# touch_pot.net
KiCad netlist of a schematic drawn in EAGLE
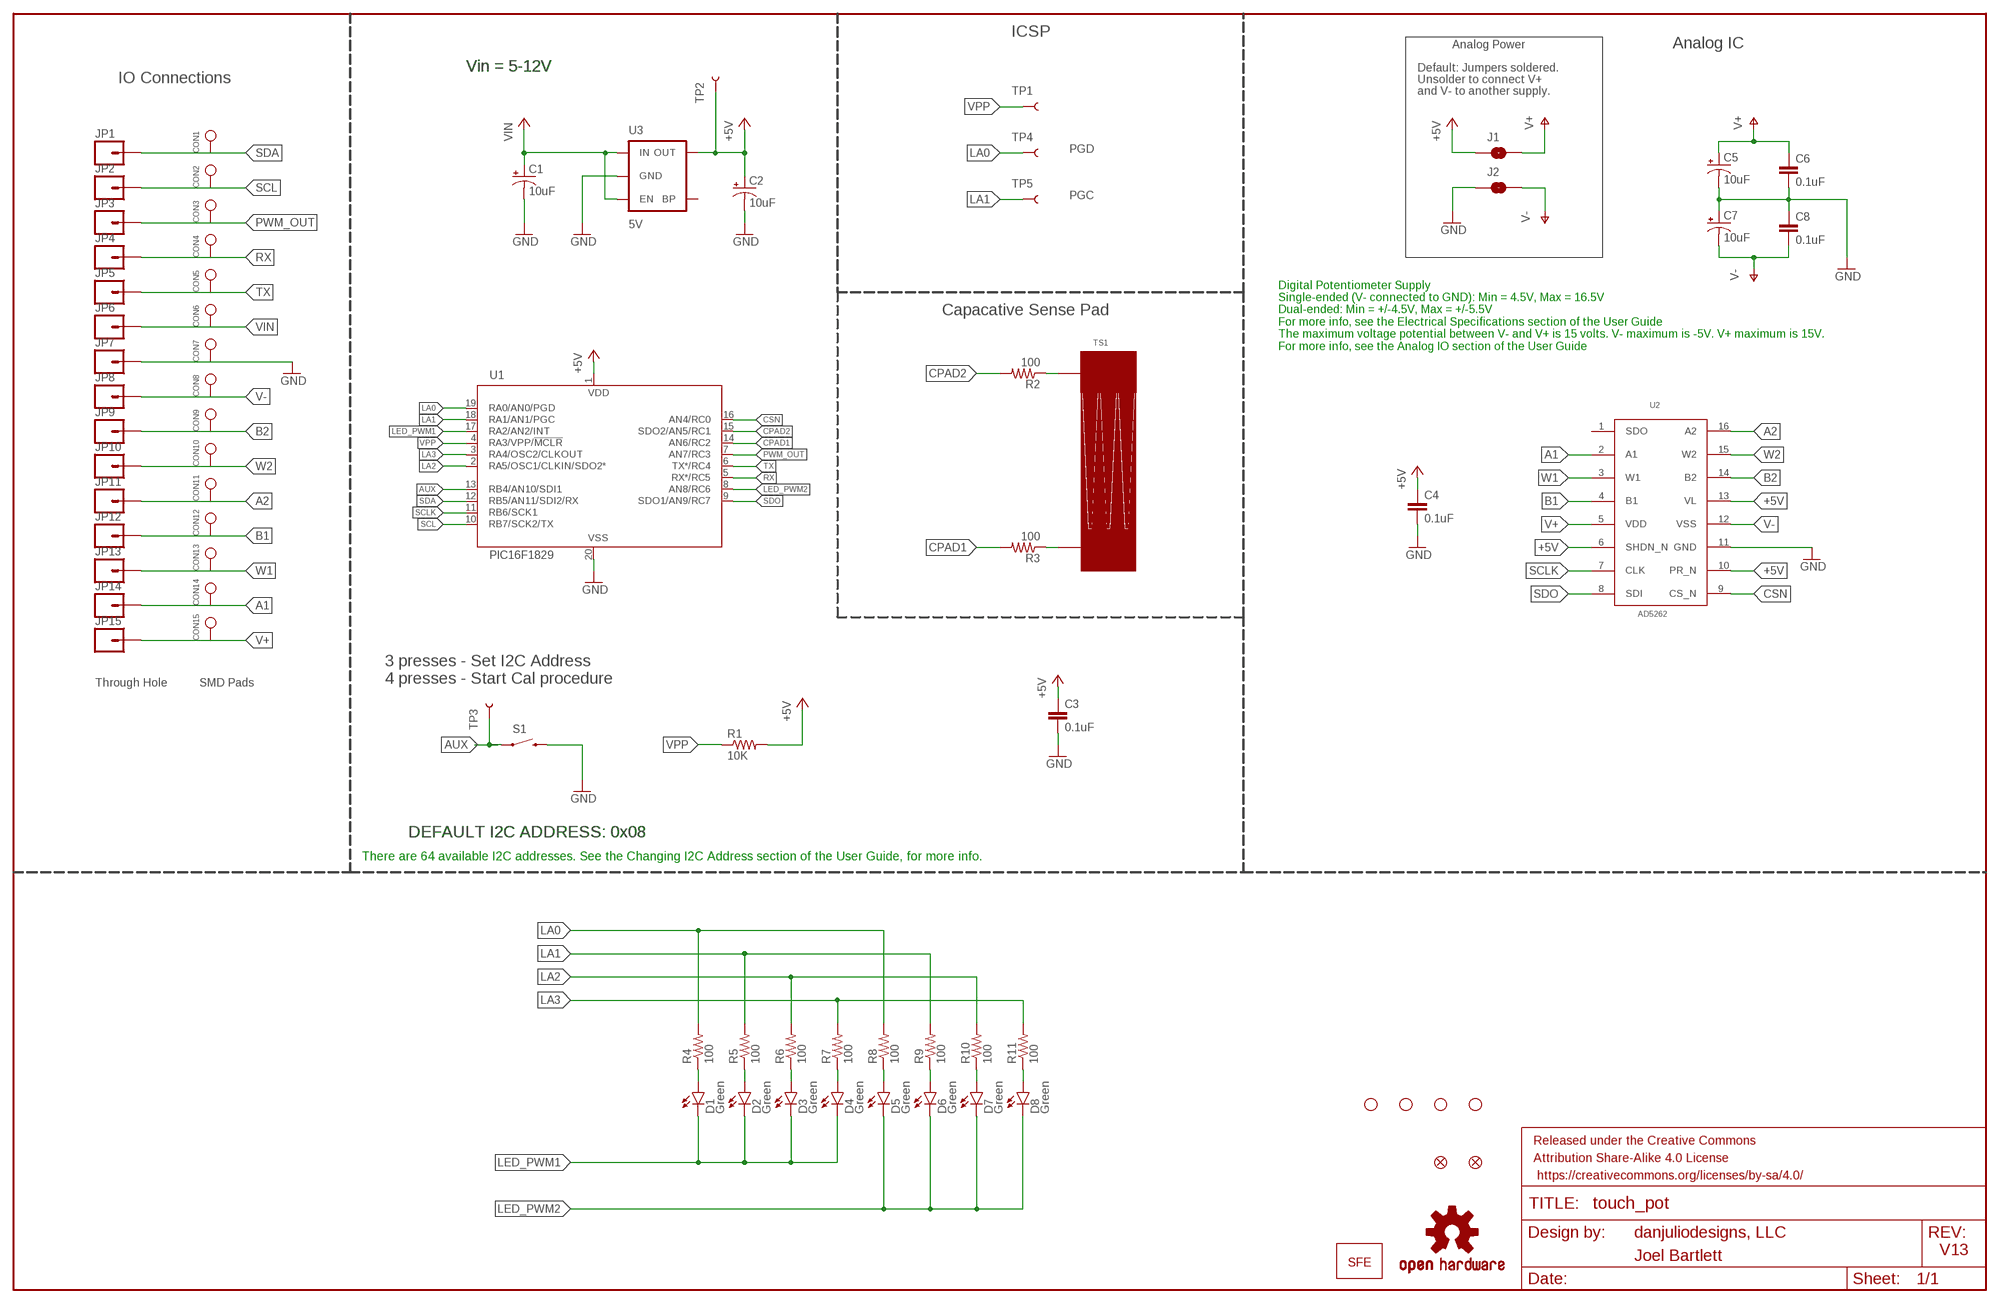
[diagram p0: schematic, sheet 1]

(export (version "E")
  (design (tool "Eeschema 10.0.6"))
  (components
    (comp (ref "C1")
      (value "10uF")
      (footprint "eagle-import:EIA3216")
      (libsource (lib "eagle-import") (part "10UF-16V-10%(TANT)"))
    )
    (comp (ref "C2")
      (value "10uF")
      (footprint "eagle-import:EIA3216")
      (libsource (lib "eagle-import") (part "10UF-16V-10%(TANT)"))
    )
    (comp (ref "C3")
      (value "0.1uF")
      (footprint "eagle-import:0603-CAP")
      (libsource (lib "eagle-import") (part "0.1UF-25V(+80/-20%)(0603)"))
    )
    (comp (ref "C4")
      (value "0.1uF")
      (footprint "eagle-import:0603-CAP")
      (libsource (lib "eagle-import") (part "0.1UF-25V(+80/-20%)(0603)"))
    )
    (comp (ref "C5")
      (value "10uF")
      (footprint "eagle-import:EIA3216")
      (libsource (lib "eagle-import") (part "10UF-16V-10%(TANT)"))
    )
    (comp (ref "C6")
      (value "0.1uF")
      (footprint "eagle-import:0603-CAP")
      (libsource (lib "eagle-import") (part "0.1UF-25V(+80/-20%)(0603)"))
    )
    (comp (ref "C7")
      (value "10uF")
      (footprint "eagle-import:EIA3216")
      (libsource (lib "eagle-import") (part "10UF-16V-10%(TANT)"))
    )
    (comp (ref "C8")
      (value "0.1uF")
      (footprint "eagle-import:0603-CAP")
      (libsource (lib "eagle-import") (part "0.1UF-25V(+80/-20%)(0603)"))
    )
    (comp (ref "CON1")
      (value "SINGLE_PADSMD")
      (footprint "eagle-import:2MM_SMD_PAD")
      (libsource (lib "eagle-import") (part "SINGLE_PADSMD"))
    )
    (comp (ref "CON2")
      (value "SINGLE_PADSMD")
      (footprint "eagle-import:2MM_SMD_PAD")
      (libsource (lib "eagle-import") (part "SINGLE_PADSMD"))
    )
    (comp (ref "CON3")
      (value "SINGLE_PADSMD")
      (footprint "eagle-import:2MM_SMD_PAD")
      (libsource (lib "eagle-import") (part "SINGLE_PADSMD"))
    )
    (comp (ref "CON4")
      (value "SINGLE_PADSMD")
      (footprint "eagle-import:2MM_SMD_PAD")
      (libsource (lib "eagle-import") (part "SINGLE_PADSMD"))
    )
    (comp (ref "CON5")
      (value "SINGLE_PADSMD")
      (footprint "eagle-import:2MM_SMD_PAD")
      (libsource (lib "eagle-import") (part "SINGLE_PADSMD"))
    )
    (comp (ref "CON6")
      (value "SINGLE_PADSMD")
      (footprint "eagle-import:2MM_SMD_PAD")
      (libsource (lib "eagle-import") (part "SINGLE_PADSMD"))
    )
    (comp (ref "CON7")
      (value "SINGLE_PADSMD")
      (footprint "eagle-import:2MM_SMD_PAD")
      (libsource (lib "eagle-import") (part "SINGLE_PADSMD"))
    )
    (comp (ref "CON8")
      (value "SINGLE_PADSMD")
      (footprint "eagle-import:2MM_SMD_PAD")
      (libsource (lib "eagle-import") (part "SINGLE_PADSMD"))
    )
    (comp (ref "CON9")
      (value "SINGLE_PADSMD")
      (footprint "eagle-import:2MM_SMD_PAD")
      (libsource (lib "eagle-import") (part "SINGLE_PADSMD"))
    )
    (comp (ref "CON10")
      (value "SINGLE_PADSMD")
      (footprint "eagle-import:2MM_SMD_PAD")
      (libsource (lib "eagle-import") (part "SINGLE_PADSMD"))
    )
    (comp (ref "CON11")
      (value "SINGLE_PADSMD")
      (footprint "eagle-import:2MM_SMD_PAD")
      (libsource (lib "eagle-import") (part "SINGLE_PADSMD"))
    )
    (comp (ref "CON12")
      (value "SINGLE_PADSMD")
      (footprint "eagle-import:2MM_SMD_PAD")
      (libsource (lib "eagle-import") (part "SINGLE_PADSMD"))
    )
    (comp (ref "CON13")
      (value "SINGLE_PADSMD")
      (footprint "eagle-import:2MM_SMD_PAD")
      (libsource (lib "eagle-import") (part "SINGLE_PADSMD"))
    )
    (comp (ref "CON14")
      (value "SINGLE_PADSMD")
      (footprint "eagle-import:2MM_SMD_PAD")
      (libsource (lib "eagle-import") (part "SINGLE_PADSMD"))
    )
    (comp (ref "CON15")
      (value "SINGLE_PADSMD")
      (footprint "eagle-import:2MM_SMD_PAD")
      (libsource (lib "eagle-import") (part "SINGLE_PADSMD"))
    )
    (comp (ref "D1")
      (value "Green")
      (footprint "eagle-import:LED-1206-BOTTOM")
      (libsource (lib "eagle-import") (part "LED-GREEN1206-BOTTOM"))
    )
    (comp (ref "D2")
      (value "Green")
      (footprint "eagle-import:LED-1206-BOTTOM")
      (libsource (lib "eagle-import") (part "LED-GREEN1206-BOTTOM"))
    )
    (comp (ref "D3")
      (value "Green")
      (footprint "eagle-import:LED-1206-BOTTOM")
      (libsource (lib "eagle-import") (part "LED-GREEN1206-BOTTOM"))
    )
    (comp (ref "D4")
      (value "Green")
      (footprint "eagle-import:LED-1206-BOTTOM")
      (libsource (lib "eagle-import") (part "LED-GREEN1206-BOTTOM"))
    )
    (comp (ref "D5")
      (value "Green")
      (footprint "eagle-import:LED-1206-BOTTOM")
      (libsource (lib "eagle-import") (part "LED-GREEN1206-BOTTOM"))
    )
    (comp (ref "D6")
      (value "Green")
      (footprint "eagle-import:LED-1206-BOTTOM")
      (libsource (lib "eagle-import") (part "LED-GREEN1206-BOTTOM"))
    )
    (comp (ref "D7")
      (value "Green")
      (footprint "eagle-import:LED-1206-BOTTOM")
      (libsource (lib "eagle-import") (part "LED-GREEN1206-BOTTOM"))
    )
    (comp (ref "D8")
      (value "Green")
      (footprint "eagle-import:LED-1206-BOTTOM")
      (libsource (lib "eagle-import") (part "LED-GREEN1206-BOTTOM"))
    )
    (comp (ref "FID1")
      (value "FIDUCIAL1X2")
      (footprint "eagle-import:FIDUCIAL-1X2")
      (libsource (lib "eagle-import") (part "FIDUCIAL1X2"))
    )
    (comp (ref "FID2")
      (value "FIDUCIAL1X2")
      (footprint "eagle-import:FIDUCIAL-1X2")
      (libsource (lib "eagle-import") (part "FIDUCIAL1X2"))
    )
    (comp (ref "FRAME3")
      (value "FRAME-LEDGER")
      (footprint "eagle-import:CREATIVE_COMMONS")
      (libsource (lib "eagle-import") (part "FRAME-LEDGER"))
    )
    (comp (ref "J1")
      (value "SJCLOSED")
      (footprint "eagle-import:SJ_2S")
      (libsource (lib "eagle-import") (part "SJCLOSED"))
    )
    (comp (ref "J2")
      (value "SJCLOSED")
      (footprint "eagle-import:SJ_2S")
      (libsource (lib "eagle-import") (part "SJCLOSED"))
    )
    (comp (ref "JP1")
      (value "M01SMDNS")
      (footprint "eagle-import:1X01NS")
      (libsource (lib "eagle-import") (part "M01SMDNS"))
    )
    (comp (ref "JP2")
      (value "M01SMDNS")
      (footprint "eagle-import:1X01NS")
      (libsource (lib "eagle-import") (part "M01SMDNS"))
    )
    (comp (ref "JP3")
      (value "M01SMDNS")
      (footprint "eagle-import:1X01NS")
      (libsource (lib "eagle-import") (part "M01SMDNS"))
    )
    (comp (ref "JP4")
      (value "M01SMDNS")
      (footprint "eagle-import:1X01NS")
      (libsource (lib "eagle-import") (part "M01SMDNS"))
    )
    (comp (ref "JP5")
      (value "M01SMDNS")
      (footprint "eagle-import:1X01NS")
      (libsource (lib "eagle-import") (part "M01SMDNS"))
    )
    (comp (ref "JP6")
      (value "M01SMDNS")
      (footprint "eagle-import:1X01NS")
      (libsource (lib "eagle-import") (part "M01SMDNS"))
    )
    (comp (ref "JP7")
      (value "M01SMDNS")
      (footprint "eagle-import:1X01NS")
      (libsource (lib "eagle-import") (part "M01SMDNS"))
    )
    (comp (ref "JP8")
      (value "M01SMDNS")
      (footprint "eagle-import:1X01NS")
      (libsource (lib "eagle-import") (part "M01SMDNS"))
    )
    (comp (ref "JP9")
      (value "M01SMDNS")
      (footprint "eagle-import:1X01NS")
      (libsource (lib "eagle-import") (part "M01SMDNS"))
    )
    (comp (ref "JP10")
      (value "M01SMDNS")
      (footprint "eagle-import:1X01NS")
      (libsource (lib "eagle-import") (part "M01SMDNS"))
    )
    (comp (ref "JP11")
      (value "M01SMDNS")
      (footprint "eagle-import:1X01NS")
      (libsource (lib "eagle-import") (part "M01SMDNS"))
    )
    (comp (ref "JP12")
      (value "M01SMDNS")
      (footprint "eagle-import:1X01NS")
      (libsource (lib "eagle-import") (part "M01SMDNS"))
    )
    (comp (ref "JP13")
      (value "M01SMDNS")
      (footprint "eagle-import:1X01NS")
      (libsource (lib "eagle-import") (part "M01SMDNS"))
    )
    (comp (ref "JP14")
      (value "M01SMDNS")
      (footprint "eagle-import:1X01NS")
      (libsource (lib "eagle-import") (part "M01SMDNS"))
    )
    (comp (ref "JP15")
      (value "M01SMDNS")
      (footprint "eagle-import:1X01NS")
      (libsource (lib "eagle-import") (part "M01SMDNS"))
    )
    (comp (ref "R1")
      (value "10K")
      (footprint "eagle-import:0603-RES")
      (libsource (lib "eagle-import") (part "10KOHM-1/10W-1%(0603)0603"))
    )
    (comp (ref "R2")
      (value "100")
      (footprint "eagle-import:0603-RES")
      (libsource (lib "eagle-import") (part "100OHM-1/10W-1%(0603)"))
    )
    (comp (ref "R3")
      (value "100")
      (footprint "eagle-import:0603-RES")
      (libsource (lib "eagle-import") (part "100OHM-1/10W-1%(0603)"))
    )
    (comp (ref "R4")
      (value "100")
      (footprint "eagle-import:0603-RES")
      (libsource (lib "eagle-import") (part "100OHM-1/10W-1%(0603)"))
    )
    (comp (ref "R5")
      (value "100")
      (footprint "eagle-import:0603-RES")
      (libsource (lib "eagle-import") (part "100OHM-1/10W-1%(0603)"))
    )
    (comp (ref "R6")
      (value "100")
      (footprint "eagle-import:0603-RES")
      (libsource (lib "eagle-import") (part "100OHM-1/10W-1%(0603)"))
    )
    (comp (ref "R7")
      (value "100")
      (footprint "eagle-import:0603-RES")
      (libsource (lib "eagle-import") (part "100OHM-1/10W-1%(0603)"))
    )
    (comp (ref "R8")
      (value "100")
      (footprint "eagle-import:0603-RES")
      (libsource (lib "eagle-import") (part "100OHM-1/10W-1%(0603)"))
    )
    (comp (ref "R9")
      (value "100")
      (footprint "eagle-import:0603-RES")
      (libsource (lib "eagle-import") (part "100OHM-1/10W-1%(0603)"))
    )
    (comp (ref "R10")
      (value "100")
      (footprint "eagle-import:0603-RES")
      (libsource (lib "eagle-import") (part "100OHM-1/10W-1%(0603)"))
    )
    (comp (ref "R11")
      (value "100")
      (footprint "eagle-import:0603-RES")
      (libsource (lib "eagle-import") (part "100OHM-1/10W-1%(0603)"))
    )
    (comp (ref "S1")
      (value "SWITCH-MOMENTARY-2SMD")
      (footprint "eagle-import:TACTILE-SWITCH-SMD")
      (libsource (lib "eagle-import") (part "SWITCH-MOMENTARY-2SMD"))
    )
    (comp (ref "STANDOFF1")
      (value "STAND-OFFTIGHT")
      (footprint "eagle-import:STAND-OFF-TIGHT")
      (libsource (lib "eagle-import") (part "STAND-OFFTIGHT"))
    )
    (comp (ref "STANDOFF2")
      (value "STAND-OFFTIGHT")
      (footprint "eagle-import:STAND-OFF-TIGHT")
      (libsource (lib "eagle-import") (part "STAND-OFFTIGHT"))
    )
    (comp (ref "STANDOFF3")
      (value "STAND-OFFTIGHT")
      (footprint "eagle-import:STAND-OFF-TIGHT")
      (libsource (lib "eagle-import") (part "STAND-OFFTIGHT"))
    )
    (comp (ref "STANDOFF4")
      (value "STAND-OFFTIGHT")
      (footprint "eagle-import:STAND-OFF-TIGHT")
      (libsource (lib "eagle-import") (part "STAND-OFFTIGHT"))
    )
    (comp (ref "TP1")
      (value "TEST-POINT3X4")
      (footprint "eagle-import:PAD.03X.04")
      (libsource (lib "eagle-import") (part "TEST-POINT3X4"))
    )
    (comp (ref "TP2")
      (value "TEST-POINT3X4")
      (footprint "eagle-import:PAD.03X.04")
      (libsource (lib "eagle-import") (part "TEST-POINT3X4"))
    )
    (comp (ref "TP3")
      (value "TEST-POINT3X4")
      (footprint "eagle-import:PAD.03X.04")
      (libsource (lib "eagle-import") (part "TEST-POINT3X4"))
    )
    (comp (ref "TP4")
      (value "TEST-POINT3X4")
      (footprint "eagle-import:PAD.03X.04")
      (libsource (lib "eagle-import") (part "TEST-POINT3X4"))
    )
    (comp (ref "TP5")
      (value "TEST-POINT3X4")
      (footprint "eagle-import:PAD.03X.04")
      (libsource (lib "eagle-import") (part "TEST-POINT3X4"))
    )
    (comp (ref "TS1")
      (value "2CH_LINEAR_TOUCH")
      (footprint "eagle-import:2CH_48MM_LINEAR_TOUCH")
      (libsource (lib "eagle-import") (part "2CH_LINEAR_TOUCH"))
    )
    (comp (ref "U$4")
      (value "OSHW-LOGOM")
      (footprint "eagle-import:OSHW-LOGO-M")
      (libsource (lib "eagle-import") (part "OSHW-LOGOM"))
    )
    (comp (ref "U$5")
      (value "SFE_LOGO_NAME_WEB")
      (footprint "eagle-import:SFE-NEW-WEBLOGO")
      (libsource (lib "eagle-import") (part "SFE_LOGO_NAME_WEB"))
    )
    (comp (ref "U1")
      (value "PIC16F1829")
      (footprint "eagle-import:SSOP20")
      (libsource (lib "eagle-import") (part "PIC16F1829"))
    )
    (comp (ref "U2")
      (value "AD5262")
      (footprint "eagle-import:SSOP16")
      (libsource (lib "eagle-import") (part "AD5262"))
    )
    (comp (ref "U3")
      (value "5V")
      (footprint "eagle-import:SOT23-5")
      (libsource (lib "eagle-import") (part "V_REG_MIC52055V"))
    )
  )
  (nets
    (net (code "1") (name "+5V") (class "Default")
      (node (ref "C2") (pin "A") (pinfunction "+_A") (pintype "passive"))
      (node (ref "C3") (pin "1") (pinfunction "1_1") (pintype "passive"))
      (node (ref "C4") (pin "1") (pinfunction "1_1") (pintype "passive"))
      (node (ref "J1") (pin "1") (pinfunction "1_1") (pintype "passive"))
      (node (ref "R1") (pin "2") (pinfunction "2_2") (pintype "passive"))
      (node (ref "TP2") (pin "P$1") (pinfunction "1_P$1") (pintype "bidirectional"))
      (node (ref "U1") (pin "1") (pinfunction "VDD_1") (pintype "power_in"))
      (node (ref "U2") (pin "10") (pinfunction "PR_N_10") (pintype "input"))
      (node (ref "U2") (pin "13") (pinfunction "VL_13") (pintype "power_in"))
      (node (ref "U2") (pin "6") (pinfunction "SHDN_N_6") (pintype "input"))
      (node (ref "U3") (pin "5") (pinfunction "OUT_5") (pintype "passive"))
    )
    (net (code "2") (name "A1") (class "Default")
      (node (ref "CON14") (pin "P$1") (pinfunction "P$1_P$1") (pintype "passive"))
      (node (ref "JP14") (pin "1") (pinfunction "1_1") (pintype "passive"))
      (node (ref "U2") (pin "2") (pinfunction "A1_2") (pintype "passive"))
    )
    (net (code "3") (name "A2") (class "Default")
      (node (ref "CON11") (pin "P$1") (pinfunction "P$1_P$1") (pintype "passive"))
      (node (ref "JP11") (pin "1") (pinfunction "1_1") (pintype "passive"))
      (node (ref "U2") (pin "16") (pinfunction "A2_16") (pintype "passive"))
    )
    (net (code "4") (name "AUX") (class "Default")
      (node (ref "S1") (pin "1") (pinfunction "1_1") (pintype "passive"))
      (node (ref "TP3") (pin "P$1") (pinfunction "1_P$1") (pintype "bidirectional"))
      (node (ref "U1") (pin "13") (pinfunction "RB4/AN10/SDI1_13") (pintype "bidirectional"))
    )
    (net (code "5") (name "B1") (class "Default")
      (node (ref "CON12") (pin "P$1") (pinfunction "P$1_P$1") (pintype "passive"))
      (node (ref "JP12") (pin "1") (pinfunction "1_1") (pintype "passive"))
      (node (ref "U2") (pin "4") (pinfunction "B1_4") (pintype "passive"))
    )
    (net (code "6") (name "B2") (class "Default")
      (node (ref "CON9") (pin "P$1") (pinfunction "P$1_P$1") (pintype "passive"))
      (node (ref "JP9") (pin "1") (pinfunction "1_1") (pintype "passive"))
      (node (ref "U2") (pin "14") (pinfunction "B2_14") (pintype "passive"))
    )
    (net (code "7") (name "CPAD1") (class "Default")
      (node (ref "R3") (pin "2") (pinfunction "2_2") (pintype "passive"))
      (node (ref "U1") (pin "14") (pinfunction "AN6/RC2_14") (pintype "bidirectional"))
    )
    (net (code "8") (name "CPAD2") (class "Default")
      (node (ref "R2") (pin "2") (pinfunction "2_2") (pintype "passive"))
      (node (ref "U1") (pin "15") (pinfunction "SDO2/AN5/RC1_15") (pintype "bidirectional"))
    )
    (net (code "9") (name "CSN") (class "Default")
      (node (ref "U1") (pin "16") (pinfunction "AN4/RC0_16") (pintype "bidirectional"))
      (node (ref "U2") (pin "9") (pinfunction "CS_N_9") (pintype "input"))
    )
    (net (code "10") (name "GND") (class "Default")
      (node (ref "C1") (pin "C") (pinfunction "-_C") (pintype "passive"))
      (node (ref "C2") (pin "C") (pinfunction "-_C") (pintype "passive"))
      (node (ref "C3") (pin "2") (pinfunction "2_2") (pintype "passive"))
      (node (ref "C4") (pin "2") (pinfunction "2_2") (pintype "passive"))
      (node (ref "C5") (pin "C") (pinfunction "-_C") (pintype "passive"))
      (node (ref "C6") (pin "2") (pinfunction "2_2") (pintype "passive"))
      (node (ref "C7") (pin "A") (pinfunction "+_A") (pintype "passive"))
      (node (ref "C8") (pin "1") (pinfunction "1_1") (pintype "passive"))
      (node (ref "CON7") (pin "P$1") (pinfunction "P$1_P$1") (pintype "passive"))
      (node (ref "J2") (pin "1") (pinfunction "1_1") (pintype "passive"))
      (node (ref "JP7") (pin "1") (pinfunction "1_1") (pintype "passive"))
      (node (ref "S1") (pin "3") (pinfunction "2_3") (pintype "passive"))
      (node (ref "U1") (pin "20") (pinfunction "VSS_20") (pintype "power_in"))
      (node (ref "U2") (pin "11") (pinfunction "GND_11") (pintype "power_in"))
      (node (ref "U3") (pin "2") (pinfunction "GND_2") (pintype "input"))
    )
    (net (code "11") (name "LA0") (class "Default")
      (node (ref "R4") (pin "2") (pinfunction "2_2") (pintype "passive"))
      (node (ref "R8") (pin "2") (pinfunction "2_2") (pintype "passive"))
      (node (ref "TP4") (pin "P$1") (pinfunction "1_P$1") (pintype "bidirectional"))
      (node (ref "U1") (pin "19") (pinfunction "RA0/AN0/PGD_19") (pintype "bidirectional"))
    )
    (net (code "12") (name "LA1") (class "Default")
      (node (ref "R5") (pin "2") (pinfunction "2_2") (pintype "passive"))
      (node (ref "R9") (pin "2") (pinfunction "2_2") (pintype "passive"))
      (node (ref "TP5") (pin "P$1") (pinfunction "1_P$1") (pintype "bidirectional"))
      (node (ref "U1") (pin "18") (pinfunction "RA1/AN1/PGC_18") (pintype "bidirectional"))
    )
    (net (code "13") (name "LA2") (class "Default")
      (node (ref "R10") (pin "2") (pinfunction "2_2") (pintype "passive"))
      (node (ref "R6") (pin "2") (pinfunction "2_2") (pintype "passive"))
      (node (ref "U1") (pin "2") (pinfunction "RA5/OSC1/CLKIN/SDO2*_2") (pintype "bidirectional"))
    )
    (net (code "14") (name "LA3") (class "Default")
      (node (ref "R11") (pin "2") (pinfunction "2_2") (pintype "passive"))
      (node (ref "R7") (pin "2") (pinfunction "2_2") (pintype "passive"))
      (node (ref "U1") (pin "3") (pinfunction "RA4/OSC2/CLKOUT_3") (pintype "bidirectional"))
    )
    (net (code "15") (name "LED_PWM1") (class "Default")
      (node (ref "D1") (pin "C") (pinfunction "C_C") (pintype "passive"))
      (node (ref "D2") (pin "C") (pinfunction "C_C") (pintype "passive"))
      (node (ref "D3") (pin "C") (pinfunction "C_C") (pintype "passive"))
      (node (ref "D4") (pin "C") (pinfunction "C_C") (pintype "passive"))
      (node (ref "U1") (pin "17") (pinfunction "RA2/AN2/INT_17") (pintype "bidirectional"))
    )
    (net (code "16") (name "LED_PWM2") (class "Default")
      (node (ref "D5") (pin "C") (pinfunction "C_C") (pintype "passive"))
      (node (ref "D6") (pin "C") (pinfunction "C_C") (pintype "passive"))
      (node (ref "D7") (pin "C") (pinfunction "C_C") (pintype "passive"))
      (node (ref "D8") (pin "C") (pinfunction "C_C") (pintype "passive"))
      (node (ref "U1") (pin "8") (pinfunction "AN8/RC6_8") (pintype "bidirectional"))
    )
    (net (code "17") (name "Net-(D1-PadA)") (class "Default")
      (node (ref "D1") (pin "A") (pinfunction "A_A") (pintype "passive"))
      (node (ref "R4") (pin "1") (pinfunction "1_1") (pintype "passive"))
    )
    (net (code "18") (name "Net-(D2-PadA)") (class "Default")
      (node (ref "D2") (pin "A") (pinfunction "A_A") (pintype "passive"))
      (node (ref "R5") (pin "1") (pinfunction "1_1") (pintype "passive"))
    )
    (net (code "19") (name "Net-(D3-PadA)") (class "Default")
      (node (ref "D3") (pin "A") (pinfunction "A_A") (pintype "passive"))
      (node (ref "R6") (pin "1") (pinfunction "1_1") (pintype "passive"))
    )
    (net (code "20") (name "Net-(D4-PadA)") (class "Default")
      (node (ref "D4") (pin "A") (pinfunction "A_A") (pintype "passive"))
      (node (ref "R7") (pin "1") (pinfunction "1_1") (pintype "passive"))
    )
    (net (code "21") (name "Net-(D5-PadA)") (class "Default")
      (node (ref "D5") (pin "A") (pinfunction "A_A") (pintype "passive"))
      (node (ref "R8") (pin "1") (pinfunction "1_1") (pintype "passive"))
    )
    (net (code "22") (name "Net-(D6-PadA)") (class "Default")
      (node (ref "D6") (pin "A") (pinfunction "A_A") (pintype "passive"))
      (node (ref "R9") (pin "1") (pinfunction "1_1") (pintype "passive"))
    )
    (net (code "23") (name "Net-(D7-PadA)") (class "Default")
      (node (ref "D7") (pin "A") (pinfunction "A_A") (pintype "passive"))
      (node (ref "R10") (pin "1") (pinfunction "1_1") (pintype "passive"))
    )
    (net (code "24") (name "Net-(D8-PadA)") (class "Default")
      (node (ref "D8") (pin "A") (pinfunction "A_A") (pintype "passive"))
      (node (ref "R11") (pin "1") (pinfunction "1_1") (pintype "passive"))
    )
    (net (code "25") (name "Net-(R2-Pad1)") (class "Default")
      (node (ref "R2") (pin "1") (pinfunction "1_1") (pintype "passive"))
      (node (ref "TS1") (pin "P$2") (pinfunction "P$2_P$2") (pintype "bidirectional"))
    )
    (net (code "26") (name "Net-(R3-Pad1)") (class "Default")
      (node (ref "R3") (pin "1") (pinfunction "1_1") (pintype "passive"))
      (node (ref "TS1") (pin "P$1") (pinfunction "P$1_P$1") (pintype "bidirectional"))
    )
    (net (code "27") (name "PWM_OUT") (class "Default")
      (node (ref "CON3") (pin "P$1") (pinfunction "P$1_P$1") (pintype "passive"))
      (node (ref "JP3") (pin "1") (pinfunction "1_1") (pintype "passive"))
      (node (ref "U1") (pin "7") (pinfunction "AN7/RC3_7") (pintype "bidirectional"))
    )
    (net (code "28") (name "RX") (class "Default")
      (node (ref "CON4") (pin "P$1") (pinfunction "P$1_P$1") (pintype "passive"))
      (node (ref "JP4") (pin "1") (pinfunction "1_1") (pintype "passive"))
      (node (ref "U1") (pin "5") (pinfunction "RX*/RC5_5") (pintype "bidirectional"))
    )
    (net (code "29") (name "SCL") (class "Default")
      (node (ref "CON2") (pin "P$1") (pinfunction "P$1_P$1") (pintype "passive"))
      (node (ref "JP2") (pin "1") (pinfunction "1_1") (pintype "passive"))
      (node (ref "U1") (pin "10") (pinfunction "RB7/SCK2/TX_10") (pintype "bidirectional"))
    )
    (net (code "30") (name "SCLK") (class "Default")
      (node (ref "U1") (pin "11") (pinfunction "RB6/SCK1_11") (pintype "bidirectional"))
      (node (ref "U2") (pin "7") (pinfunction "CLK_7") (pintype "input"))
    )
    (net (code "31") (name "SDA") (class "Default")
      (node (ref "CON1") (pin "P$1") (pinfunction "P$1_P$1") (pintype "passive"))
      (node (ref "JP1") (pin "1") (pinfunction "1_1") (pintype "passive"))
      (node (ref "U1") (pin "12") (pinfunction "RB5/AN11/SDI2/RX_12") (pintype "bidirectional"))
    )
    (net (code "32") (name "SDO") (class "Default")
      (node (ref "U1") (pin "9") (pinfunction "SDO1/AN9/RC7_9") (pintype "bidirectional"))
      (node (ref "U2") (pin "8") (pinfunction "SDI_8") (pintype "input"))
    )
    (net (code "33") (name "TX") (class "Default")
      (node (ref "CON5") (pin "P$1") (pinfunction "P$1_P$1") (pintype "passive"))
      (node (ref "JP5") (pin "1") (pinfunction "1_1") (pintype "passive"))
      (node (ref "U1") (pin "6") (pinfunction "TX*/RC4_6") (pintype "bidirectional"))
    )
    (net (code "34") (name "V+") (class "Default")
      (node (ref "C5") (pin "A") (pinfunction "+_A") (pintype "passive"))
      (node (ref "C6") (pin "1") (pinfunction "1_1") (pintype "passive"))
      (node (ref "CON15") (pin "P$1") (pinfunction "P$1_P$1") (pintype "passive"))
      (node (ref "J1") (pin "2") (pinfunction "2_2") (pintype "passive"))
      (node (ref "JP15") (pin "1") (pinfunction "1_1") (pintype "passive"))
      (node (ref "U2") (pin "5") (pinfunction "VDD_5") (pintype "power_in"))
    )
    (net (code "35") (name "V-") (class "Default")
      (node (ref "C7") (pin "C") (pinfunction "-_C") (pintype "passive"))
      (node (ref "C8") (pin "2") (pinfunction "2_2") (pintype "passive"))
      (node (ref "CON8") (pin "P$1") (pinfunction "P$1_P$1") (pintype "passive"))
      (node (ref "J2") (pin "2") (pinfunction "2_2") (pintype "passive"))
      (node (ref "JP8") (pin "1") (pinfunction "1_1") (pintype "passive"))
      (node (ref "U2") (pin "12") (pinfunction "VSS_12") (pintype "power_in"))
    )
    (net (code "36") (name "VIN") (class "Default")
      (node (ref "C1") (pin "A") (pinfunction "+_A") (pintype "passive"))
      (node (ref "CON6") (pin "P$1") (pinfunction "P$1_P$1") (pintype "passive"))
      (node (ref "JP6") (pin "1") (pinfunction "1_1") (pintype "passive"))
      (node (ref "U3") (pin "1") (pinfunction "IN_1") (pintype "input"))
      (node (ref "U3") (pin "3") (pinfunction "EN_3") (pintype "input"))
    )
    (net (code "37") (name "VPP") (class "Default")
      (node (ref "R1") (pin "1") (pinfunction "1_1") (pintype "passive"))
      (node (ref "TP1") (pin "P$1") (pinfunction "1_P$1") (pintype "bidirectional"))
      (node (ref "U1") (pin "4") (pinfunction "RA3/VPP/~{MCLR}_4") (pintype "input"))
    )
    (net (code "38") (name "W1") (class "Default")
      (node (ref "CON13") (pin "P$1") (pinfunction "P$1_P$1") (pintype "passive"))
      (node (ref "JP13") (pin "1") (pinfunction "1_1") (pintype "passive"))
      (node (ref "U2") (pin "3") (pinfunction "W1_3") (pintype "passive"))
    )
    (net (code "39") (name "W2") (class "Default")
      (node (ref "CON10") (pin "P$1") (pinfunction "P$1_P$1") (pintype "passive"))
      (node (ref "JP10") (pin "1") (pinfunction "1_1") (pintype "passive"))
      (node (ref "U2") (pin "15") (pinfunction "W2_15") (pintype "passive"))
    )
    (net (code "40") (name "unconnected-(U2-SDO-Pad1)") (class "Default")
      (node (ref "U2") (pin "1") (pinfunction "SDO_1") (pintype "output"))
    )
    (net (code "41") (name "unconnected-(U3-BP-Pad4)") (class "Default")
      (node (ref "U3") (pin "4") (pinfunction "BP_4") (pintype "input"))
    )
  )
)
